# battery-charging.net
KiCad netlist of a schematic drawn in Altium Designer
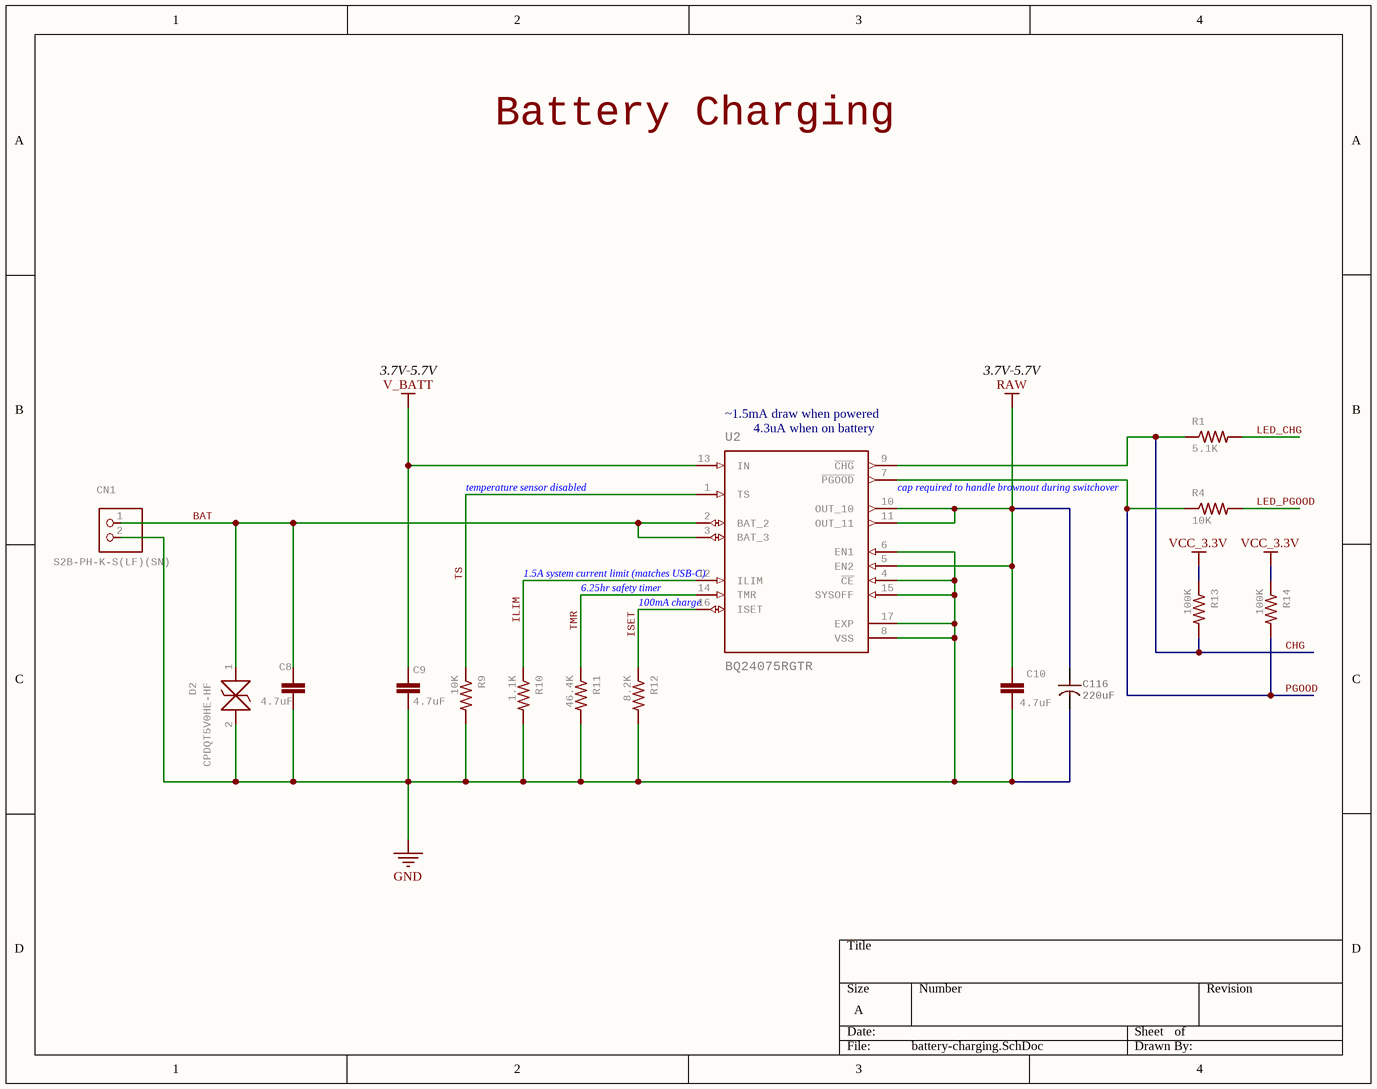
[diagram p0: battery-charging.SchDoc]

(export (version "E")
  (design (tool "Eeschema 10.0.6"))
  (components
    (comp (ref "C8")
      (value "4.7uF")
      (footprint "0402-CAP")
      (description "CapacitorStandard 0603 ceramic capacitor, and 0.1\" leaded capacitor.")
      (fields (field (name "MPN") "JMK105BBJ475MV-F") (field (name "LIBRARYNAME") "sfe"))
      (libsource (lib "openmv-ae3") (part "CAP0402-CAP"))
    )
    (comp (ref "C9")
      (value "4.7uF")
      (footprint "0402-CAP")
      (description "CapacitorStandard 0603 ceramic capacitor, and 0.1\" leaded capacitor.")
      (fields (field (name "MPN") "JMK105BBJ475MV-F") (field (name "LIBRARYNAME") "sfe"))
      (libsource (lib "openmv-ae3") (part "CAP0402-CAP"))
    )
    (comp (ref "C10")
      (value "4.7uF")
      (footprint "0402-CAP")
      (description "CapacitorStandard 0603 ceramic capacitor, and 0.1\" leaded capacitor.")
      (fields (field (name "MPN") "JMK105BBJ475MV-F") (field (name "LIBRARYNAME") "sfe"))
      (libsource (lib "openmv-ae3") (part "CAP0402-CAP"))
    )
    (comp (ref "C116")
      (value "220uF")
      (footprint "CAP-TANT-1411")
      (fields (field (name "PART NUMBER") "F930J227MBA"))
      (libsource (lib "openmv-ae3") (part "CAP_POL"))
    )
    (comp (ref "CN1")
      (value "S2B-PH-K-S(LF)(SN)")
      (footprint "JST-PH-2-THM-RA")
      (fields (field (name "LIBRARYNAME") "adafruit-updated"))
      (libsource (lib "openmv-ae3") (part "JST_2PIN-THM-RA"))
    )
    (comp (ref "D2")
      (value "CPDQT5V0HE-HF")
      (footprint "CPDQT5V0HEHF")
      (description "ESD Suppressors / TVS Diodes DIODE ESD 5VWM 65W 0402/SOD-923F   Source:  Datasheet")
      (fields (field (name "MOUSER_PART_NUMBER") "MOUSER_PART_NUMBER"))
      (libsource (lib "openmv-ae3") (part "CPDQT5V0HE-HF"))
    )
    (comp (ref "R1")
      (value "5.1K")
      (footprint "R0201")
      (fields (field (name "LIBRARYNAME") "sfe"))
      (libsource (lib "openmv-ae3") (part "RESISTOR0402-RES"))
    )
    (comp (ref "R4")
      (value "10K")
      (footprint "R0201")
      (fields (field (name "LIBRARYNAME") "sfe"))
      (libsource (lib "openmv-ae3") (part "RESISTOR0402-RES"))
    )
    (comp (ref "R9")
      (value "10K")
      (footprint "0402-RES")
      (description "ResistorBasic schematic elements and footprints for 0603, 1206, and PTH resistors.")
      (fields (field (name "MPN") "AC0402FR-1310KL") (field (name "LIBRARYNAME") "sfe"))
      (libsource (lib "openmv-ae3") (part "RESISTOR0402-RES"))
    )
    (comp (ref "R10")
      (value "1.1K")
      (footprint "0402-RES")
      (description "ResistorBasic schematic elements and footprints for 0603, 1206, and PTH resistors.")
      (fields (field (name "MPN") "RC0402JR-071K1") (field (name "LIBRARYNAME") "sfe"))
      (libsource (lib "openmv-ae3") (part "RESISTOR0402-RES"))
    )
    (comp (ref "R11")
      (value "46.4K")
      (footprint "0402-RES")
      (description "ResistorBasic schematic elements and footprints for 0603, 1206, and PTH resistors.")
      (fields (field (name "MPN") "WR04X4642FTL") (field (name "LIBRARYNAME") "sfe"))
      (libsource (lib "openmv-ae3") (part "RESISTOR0402-RES"))
    )
    (comp (ref "R12")
      (value "8.2K")
      (footprint "0402-RES")
      (description "ResistorBasic schematic elements and footprints for 0603, 1206, and PTH resistors.")
      (fields (field (name "MPN") "CR0402-FX-8201GLF") (field (name "LIBRARYNAME") "sfe"))
      (libsource (lib "openmv-ae3") (part "RESISTOR0402-RES"))
    )
    (comp (ref "R13")
      (value "100K")
      (footprint "R0201")
      (fields (field (name "LIBRARYNAME") "sfe"))
      (libsource (lib "openmv-ae3") (part "RESISTOR0402-RES"))
    )
    (comp (ref "R14")
      (value "100K")
      (footprint "R0201")
      (fields (field (name "LIBRARYNAME") "sfe"))
      (libsource (lib "openmv-ae3") (part "RESISTOR0402-RES"))
    )
    (comp (ref "U2")
      (value "BQ24075RGTR")
      (footprint "QFN50P300X300X100-17N")
      (fields (field (name "MF") "Texas Instruments"))
      (libsource (lib "openmv-ae3") (part "BQ24075RGTR"))
    )
  )
  (nets
    (net (code "1") (name "/BAT") (class "Default")
      (node (ref "C8") (pin "2") (pinfunction "2_2") (pintype "passive"))
      (node (ref "CN1") (pin "1") (pinfunction "2_1") (pintype "passive"))
      (node (ref "D2") (pin "1") (pinfunction "1_1") (pintype "bidirectional"))
      (node (ref "U2") (pin "2") (pinfunction "BAT_2_2") (pintype "bidirectional"))
      (node (ref "U2") (pin "3") (pinfunction "BAT_3_3") (pintype "bidirectional"))
    )
    (net (code "2") (name "/CHG") (class "Default")
      (node (ref "R1") (pin "1") (pinfunction "1_1") (pintype "passive"))
      (node (ref "R13") (pin "2") (pinfunction "2_2") (pintype "passive"))
      (node (ref "U2") (pin "9") (pinfunction "~{CHG}_9") (pintype "output"))
    )
    (net (code "3") (name "/ILIM") (class "Default")
      (node (ref "R10") (pin "1") (pinfunction "1_1") (pintype "passive"))
      (node (ref "U2") (pin "12") (pinfunction "ILIM_12") (pintype "input"))
    )
    (net (code "4") (name "/ISET") (class "Default")
      (node (ref "R12") (pin "1") (pinfunction "1_1") (pintype "passive"))
      (node (ref "U2") (pin "16") (pinfunction "ISET_16") (pintype "bidirectional"))
    )
    (net (code "5") (name "/LED_CHG") (class "Default")
      (node (ref "R1") (pin "2") (pinfunction "2_2") (pintype "passive"))
    )
    (net (code "6") (name "/LED_PGOOD") (class "Default")
      (node (ref "R4") (pin "2") (pinfunction "2_2") (pintype "passive"))
    )
    (net (code "7") (name "/PGOOD") (class "Default")
      (node (ref "R14") (pin "2") (pinfunction "2_2") (pintype "passive"))
      (node (ref "R4") (pin "1") (pinfunction "1_1") (pintype "passive"))
      (node (ref "U2") (pin "7") (pinfunction "~{PGOOD}_7") (pintype "output"))
    )
    (net (code "8") (name "/TMR") (class "Default")
      (node (ref "R11") (pin "1") (pinfunction "1_1") (pintype "passive"))
      (node (ref "U2") (pin "14") (pinfunction "TMR_14") (pintype "input"))
    )
    (net (code "9") (name "/TS") (class "Default")
      (node (ref "R9") (pin "1") (pinfunction "1_1") (pintype "passive"))
      (node (ref "U2") (pin "1") (pinfunction "TS_1") (pintype "input"))
    )
    (net (code "10") (name "GND") (class "Default")
      (node (ref "C10") (pin "1") (pinfunction "1_1") (pintype "passive"))
      (node (ref "C116") (pin "2") (pinfunction "2_2") (pintype "passive"))
      (node (ref "C8") (pin "1") (pinfunction "1_1") (pintype "passive"))
      (node (ref "C9") (pin "1") (pinfunction "1_1") (pintype "passive"))
      (node (ref "CN1") (pin "2") (pinfunction "1_2") (pintype "passive"))
      (node (ref "D2") (pin "2") (pinfunction "2_2") (pintype "bidirectional"))
      (node (ref "R10") (pin "2") (pinfunction "2_2") (pintype "passive"))
      (node (ref "R11") (pin "2") (pinfunction "2_2") (pintype "passive"))
      (node (ref "R12") (pin "2") (pinfunction "2_2") (pintype "passive"))
      (node (ref "R9") (pin "2") (pinfunction "2_2") (pintype "passive"))
      (node (ref "U2") (pin "15") (pinfunction "SYSOFF_15") (pintype "input"))
      (node (ref "U2") (pin "17") (pinfunction "EXP_17") (pintype "power_in"))
      (node (ref "U2") (pin "4") (pinfunction "~{CE}_4") (pintype "input"))
      (node (ref "U2") (pin "6") (pinfunction "EN1_6") (pintype "input"))
      (node (ref "U2") (pin "8") (pinfunction "VSS_8") (pintype "power_in"))
    )
    (net (code "11") (name "RAW") (class "Default")
      (node (ref "C10") (pin "2") (pinfunction "2_2") (pintype "passive"))
      (node (ref "C116") (pin "1") (pinfunction "1_1") (pintype "passive"))
      (node (ref "U2") (pin "10") (pinfunction "OUT_10_10") (pintype "output"))
      (node (ref "U2") (pin "11") (pinfunction "OUT_11_11") (pintype "output"))
      (node (ref "U2") (pin "5") (pinfunction "EN2_5") (pintype "input"))
    )
    (net (code "12") (name "VCC_3.3V") (class "Default")
      (node (ref "R13") (pin "1") (pinfunction "1_1") (pintype "passive"))
      (node (ref "R14") (pin "1") (pinfunction "1_1") (pintype "passive"))
    )
    (net (code "13") (name "V_BATT") (class "Default")
      (node (ref "C9") (pin "2") (pinfunction "2_2") (pintype "passive"))
      (node (ref "U2") (pin "13") (pinfunction "IN_13") (pintype "input"))
    )
  )
)
